# 07_AUDIO.net
KiCad netlist of a schematic drawn in Altium Designer
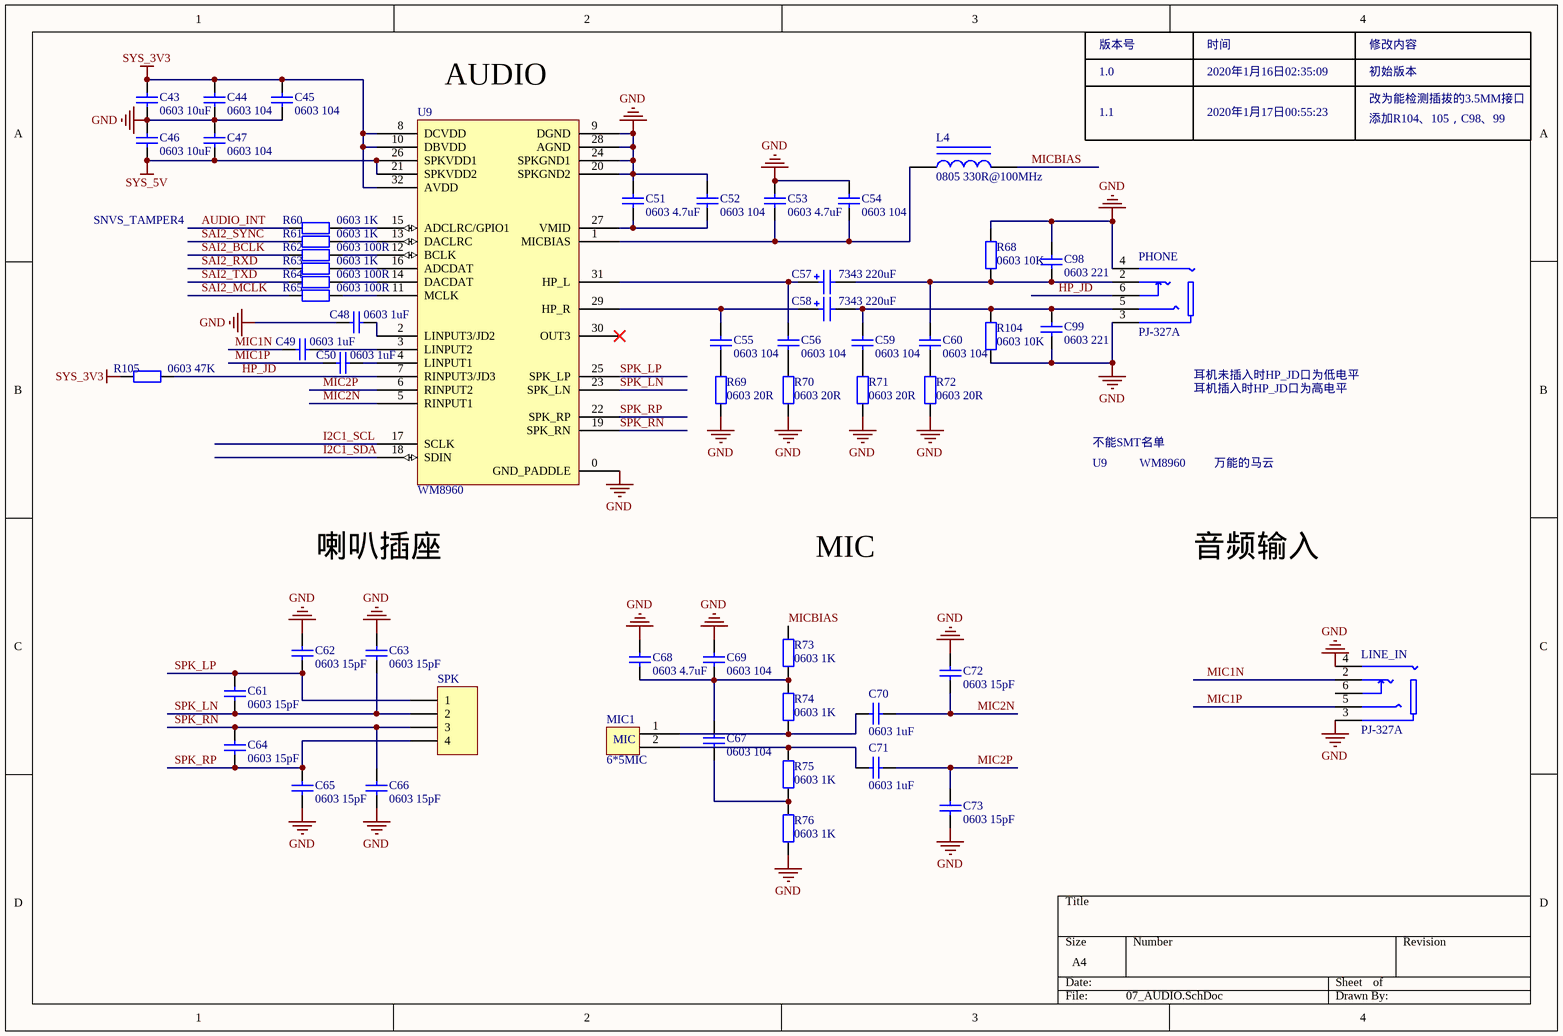
[diagram p0: 07_AUDIO.SchDoc]

(export (version "E")
  (design (tool "Eeschema 10.0.6"))
  (components
    (comp (ref "C43")
      (value "0603 10uF")
      (footprint "LC-0603_C")
      (description "贴片电容")
      (libsource (lib "JLC") (part "0603 1.5nF (152) 10% 50V"))
    )
    (comp (ref "C44")
      (value "0603 104")
      (footprint "LC-0603_C")
      (description "贴片电容")
      (libsource (lib "JLC") (part "0603 1.5nF (152) 10% 50V"))
    )
    (comp (ref "C45")
      (value "0603 104")
      (footprint "LC-0603_C")
      (description "贴片电容")
      (libsource (lib "JLC") (part "0603 1.5nF (152) 10% 50V"))
    )
    (comp (ref "C46")
      (value "0603 10uF")
      (footprint "LC-0603_C")
      (description "贴片电容")
      (libsource (lib "JLC") (part "0603 1.5nF (152) 10% 50V"))
    )
    (comp (ref "C47")
      (value "0603 104")
      (footprint "LC-0603_C")
      (description "贴片电容")
      (libsource (lib "JLC") (part "0603 1.5nF (152) 10% 50V"))
    )
    (comp (ref "C48")
      (value "0603 1uF")
      (footprint "LC-0603_C")
      (description "贴片电容")
      (libsource (lib "JLC") (part "0603 1.5nF (152) 10% 50V"))
    )
    (comp (ref "C49")
      (value "0603 1uF")
      (footprint "LC-0603_C")
      (description "贴片电容")
      (libsource (lib "JLC") (part "0603 1.5nF (152) 10% 50V"))
    )
    (comp (ref "C50")
      (value "0603 1uF")
      (footprint "LC-0603_C")
      (description "贴片电容")
      (libsource (lib "JLC") (part "0603 1.5nF (152) 10% 50V"))
    )
    (comp (ref "C51")
      (value "0603 4.7uF")
      (footprint "LC-0603_C")
      (description "贴片电容")
      (libsource (lib "JLC") (part "0603 1.5nF (152) 10% 50V"))
    )
    (comp (ref "C52")
      (value "0603 104")
      (footprint "LC-0603_C")
      (description "贴片电容")
      (libsource (lib "JLC") (part "0603 1.5nF (152) 10% 50V"))
    )
    (comp (ref "C53")
      (value "0603 4.7uF")
      (footprint "LC-0603_C")
      (description "贴片电容")
      (libsource (lib "JLC") (part "0603 1.5nF (152) 10% 50V"))
    )
    (comp (ref "C54")
      (value "0603 104")
      (footprint "LC-0603_C")
      (description "贴片电容")
      (libsource (lib "JLC") (part "0603 1.5nF (152) 10% 50V"))
    )
    (comp (ref "C55")
      (value "0603 104")
      (footprint "LC-0603_C")
      (description "贴片电容")
      (libsource (lib "JLC") (part "0603 1.5nF (152) 10% 50V"))
    )
    (comp (ref "C56")
      (value "0603 104")
      (footprint "LC-0603_C")
      (description "贴片电容")
      (libsource (lib "JLC") (part "0603 1.5nF (152) 10% 50V"))
    )
    (comp (ref "C57")
      (value "7343 220uF")
      (footprint "Ta7343")
      (libsource (lib "Integrated_Library2") (part "CAP1"))
    )
    (comp (ref "C58")
      (value "7343 220uF")
      (footprint "Ta7343")
      (libsource (lib "Integrated_Library2") (part "CAP1"))
    )
    (comp (ref "C59")
      (value "0603 104")
      (footprint "LC-0603_C")
      (description "贴片电容")
      (libsource (lib "JLC") (part "0603 1.5nF (152) 10% 50V"))
    )
    (comp (ref "C60")
      (value "0603 104")
      (footprint "LC-0603_C")
      (description "贴片电容")
      (libsource (lib "JLC") (part "0603 1.5nF (152) 10% 50V"))
    )
    (comp (ref "C61")
      (value "0603 15pF")
      (footprint "LC-0603_C")
      (description "贴片电容")
      (libsource (lib "JLC") (part "0603 1.5nF (152) 10% 50V"))
    )
    (comp (ref "C62")
      (value "0603 15pF")
      (footprint "LC-0603_C")
      (description "贴片电容")
      (libsource (lib "JLC") (part "0603 1.5nF (152) 10% 50V"))
    )
    (comp (ref "C63")
      (value "0603 15pF")
      (footprint "LC-0603_C")
      (description "贴片电容")
      (libsource (lib "JLC") (part "0603 1.5nF (152) 10% 50V"))
    )
    (comp (ref "C64")
      (value "0603 15pF")
      (footprint "LC-0603_C")
      (description "贴片电容")
      (libsource (lib "JLC") (part "0603 1.5nF (152) 10% 50V"))
    )
    (comp (ref "C65")
      (value "0603 15pF")
      (footprint "LC-0603_C")
      (description "贴片电容")
      (libsource (lib "JLC") (part "0603 1.5nF (152) 10% 50V"))
    )
    (comp (ref "C66")
      (value "0603 15pF")
      (footprint "LC-0603_C")
      (description "贴片电容")
      (libsource (lib "JLC") (part "0603 1.5nF (152) 10% 50V"))
    )
    (comp (ref "C67")
      (value "0603 104")
      (footprint "LC-0603_C")
      (description "贴片电容")
      (libsource (lib "JLC") (part "0603 1.5nF (152) 10% 50V"))
    )
    (comp (ref "C68")
      (value "0603 4.7uF")
      (footprint "LC-0603_C")
      (description "贴片电容")
      (libsource (lib "JLC") (part "0603 1.5nF (152) 10% 50V"))
    )
    (comp (ref "C69")
      (value "0603 104")
      (footprint "LC-0603_C")
      (description "贴片电容")
      (libsource (lib "JLC") (part "0603 1.5nF (152) 10% 50V"))
    )
    (comp (ref "C70")
      (value "0603 1uF")
      (footprint "LC-0603_C")
      (description "贴片电容")
      (libsource (lib "JLC") (part "0603 1.5nF (152) 10% 50V"))
    )
    (comp (ref "C71")
      (value "0603 1uF")
      (footprint "LC-0603_C")
      (description "贴片电容")
      (libsource (lib "JLC") (part "0603 1.5nF (152) 10% 50V"))
    )
    (comp (ref "C72")
      (value "0603 15pF")
      (footprint "LC-0603_C")
      (description "贴片电容")
      (libsource (lib "JLC") (part "0603 1.5nF (152) 10% 50V"))
    )
    (comp (ref "C73")
      (value "0603 15pF")
      (footprint "LC-0603_C")
      (description "贴片电容")
      (libsource (lib "JLC") (part "0603 1.5nF (152) 10% 50V"))
    )
    (comp (ref "C98")
      (value "0603 221")
      (footprint "LC-0603_C")
      (description "贴片电容")
      (libsource (lib "JLC") (part "0603 1.5nF (152) 10% 50V"))
    )
    (comp (ref "C99")
      (value "0603 221")
      (footprint "LC-0603_C")
      (description "贴片电容")
      (libsource (lib "JLC") (part "0603 1.5nF (152) 10% 50V"))
    )
    (comp (ref "L4")
      (value "0805 330R@100MHz")
      (footprint "LC-0805_L")
      (description "贴片电感")
      (libsource (lib "JLC") (part "0805 1uH 10%"))
    )
    (comp (ref "LINE_IN")
      (value "PJ-327A")
      (footprint "PJ-327A")
      (libsource (lib "Integrated_Library2") (part "PJ-327A"))
    )
    (comp (ref "MIC1")
      (value "6*5MIC")
      (footprint "6*5MIC")
      (libsource (lib "Integrated_Library2") (part "6*5MIC"))
    )
    (comp (ref "PHONE")
      (value "PJ-327A")
      (footprint "PJ-327A")
      (libsource (lib "Integrated_Library2") (part "PJ-327A"))
    )
    (comp (ref "R60")
      (value "0603 1K")
      (footprint "LC-0603_R")
      (description "贴片电阻")
      (libsource (lib "") (part "0603 1.1KΩ (1101) 1%_1"))
    )
    (comp (ref "R61")
      (value "0603 1K")
      (footprint "LC-0603_R")
      (description "贴片电阻")
      (libsource (lib "") (part "0603 1.1KΩ (1101) 1%_1"))
    )
    (comp (ref "R62")
      (value "0603 100R")
      (footprint "LC-0603_R")
      (description "贴片电阻")
      (libsource (lib "") (part "0603 1.1KΩ (1101) 1%_1"))
    )
    (comp (ref "R63")
      (value "0603 1K")
      (footprint "LC-0603_R")
      (description "贴片电阻")
      (libsource (lib "") (part "0603 1.1KΩ (1101) 1%_1"))
    )
    (comp (ref "R64")
      (value "0603 100R")
      (footprint "LC-0603_R")
      (description "贴片电阻")
      (libsource (lib "") (part "0603 1.1KΩ (1101) 1%_1"))
    )
    (comp (ref "R65")
      (value "0603 100R")
      (footprint "LC-0603_R")
      (description "贴片电阻")
      (libsource (lib "") (part "0603 1.1KΩ (1101) 1%_1"))
    )
    (comp (ref "R68")
      (value "0603 10K")
      (footprint "LC-0603_R")
      (description "贴片电阻")
      (libsource (lib "JLC") (part "0603 1.1KΩ (1101) 1%"))
    )
    (comp (ref "R69")
      (value "0603 20R")
      (footprint "LC-0603_R")
      (description "贴片电阻")
      (libsource (lib "JLC") (part "0603 1.1KΩ (1101) 1%"))
    )
    (comp (ref "R70")
      (value "0603 20R")
      (footprint "LC-0603_R")
      (description "贴片电阻")
      (libsource (lib "JLC") (part "0603 1.1KΩ (1101) 1%"))
    )
    (comp (ref "R71")
      (value "0603 20R")
      (footprint "LC-0603_R")
      (description "贴片电阻")
      (libsource (lib "JLC") (part "0603 1.1KΩ (1101) 1%"))
    )
    (comp (ref "R72")
      (value "0603 20R")
      (footprint "LC-0603_R")
      (description "贴片电阻")
      (libsource (lib "JLC") (part "0603 1.1KΩ (1101) 1%"))
    )
    (comp (ref "R73")
      (value "0603 1K")
      (footprint "LC-0603_R")
      (description "贴片电阻")
      (libsource (lib "JLC") (part "0603 1.1KΩ (1101) 1%"))
    )
    (comp (ref "R74")
      (value "0603 1K")
      (footprint "LC-0603_R")
      (description "贴片电阻")
      (libsource (lib "JLC") (part "0603 1.1KΩ (1101) 1%"))
    )
    (comp (ref "R75")
      (value "0603 1K")
      (footprint "LC-0603_R")
      (description "贴片电阻")
      (libsource (lib "JLC") (part "0603 1.1KΩ (1101) 1%"))
    )
    (comp (ref "R76")
      (value "0603 1K")
      (footprint "LC-0603_R")
      (description "贴片电阻")
      (libsource (lib "JLC") (part "0603 1.1KΩ (1101) 1%"))
    )
    (comp (ref "R104")
      (value "0603 10K")
      (footprint "LC-0603_R")
      (description "贴片电阻")
      (libsource (lib "") (part "0603 1.1KΩ (1101) 1%_2"))
    )
    (comp (ref "R105")
      (value "0603 47K")
      (footprint "LC-0603_R")
      (description "贴片电阻")
      (libsource (lib "") (part "0603 1.1KΩ (1101) 1%_1"))
    )
    (comp (ref "SPK")
      (value "~")
      (footprint "HDR1X4")
      (description "Header, 4-Pin")
      (fields (field (name "PUBLISHER") "Altium Limited"))
      (libsource (lib "Miscellaneous Connectors") (part "Header 4"))
    )
    (comp (ref "U9")
      (value "WM8960")
      (footprint "LC-QFN-32_5x5x05P")
      (libsource (lib "Integrated_Library2") (part "WM8960"))
    )
  )
  (nets
    (net (code "1") (name "/AUDIO_INT") (class "Default")
      (node (ref "R60") (pin "1") (pinfunction "1_1") (pintype "passive"))
    )
    (net (code "2") (name "/HP_JD") (class "Default")
      (node (ref "PHONE") (pin "6") (pinfunction "6_6") (pintype "passive"))
      (node (ref "R105") (pin "2") (pinfunction "2_2") (pintype "passive"))
      (node (ref "U9") (pin "7") (pinfunction "RINPUT3/JD3_7") (pintype "passive"))
    )
    (net (code "3") (name "/I2C1_SCL") (class "Default")
      (node (ref "U9") (pin "17") (pinfunction "SCLK_17") (pintype "passive"))
    )
    (net (code "4") (name "/I2C1_SDA") (class "Default")
      (node (ref "U9") (pin "18") (pinfunction "SDIN_18") (pintype "bidirectional"))
    )
    (net (code "5") (name "/MIC1N") (class "Default")
      (node (ref "C49") (pin "2") (pinfunction "2_2") (pintype "passive"))
      (node (ref "LINE_IN") (pin "2") (pinfunction "2_2") (pintype "passive"))
    )
    (net (code "6") (name "/MIC1P") (class "Default")
      (node (ref "C50") (pin "2") (pinfunction "2_2") (pintype "passive"))
      (node (ref "LINE_IN") (pin "5") (pinfunction "5_5") (pintype "passive"))
    )
    (net (code "7") (name "/MIC2N") (class "Default")
      (node (ref "C70") (pin "2") (pinfunction "2_2") (pintype "passive"))
      (node (ref "C72") (pin "1") (pinfunction "1_1") (pintype "passive"))
      (node (ref "U9") (pin "5") (pinfunction "RINPUT1_5") (pintype "passive"))
    )
    (net (code "8") (name "/MIC2P") (class "Default")
      (node (ref "C71") (pin "2") (pinfunction "2_2") (pintype "passive"))
      (node (ref "C73") (pin "2") (pinfunction "2_2") (pintype "passive"))
      (node (ref "U9") (pin "6") (pinfunction "RINPUT2_6") (pintype "passive"))
    )
    (net (code "9") (name "/MICBIAS") (class "Default")
      (node (ref "L4") (pin "2") (pinfunction "2_2") (pintype "passive"))
      (node (ref "R73") (pin "1") (pinfunction "1_1") (pintype "passive"))
    )
    (net (code "10") (name "/SAI2_BCLK") (class "Default")
      (node (ref "R62") (pin "1") (pinfunction "1_1") (pintype "passive"))
    )
    (net (code "11") (name "/SAI2_MCLK") (class "Default")
      (node (ref "R65") (pin "1") (pinfunction "1_1") (pintype "passive"))
    )
    (net (code "12") (name "/SAI2_RXD") (class "Default")
      (node (ref "R63") (pin "1") (pinfunction "1_1") (pintype "passive"))
    )
    (net (code "13") (name "/SAI2_SYNC") (class "Default")
      (node (ref "R61") (pin "1") (pinfunction "1_1") (pintype "passive"))
    )
    (net (code "14") (name "/SAI2_TXD") (class "Default")
      (node (ref "R64") (pin "1") (pinfunction "1_1") (pintype "passive"))
    )
    (net (code "15") (name "/SPK_LN") (class "Default")
      (node (ref "C61") (pin "2") (pinfunction "2_2") (pintype "passive"))
      (node (ref "C63") (pin "2") (pinfunction "2_2") (pintype "passive"))
      (node (ref "SPK") (pin "2") (pinfunction "2_2") (pintype "passive"))
      (node (ref "U9") (pin "23") (pinfunction "SPK_LN_23") (pintype "passive"))
    )
    (net (code "16") (name "/SPK_LP") (class "Default")
      (node (ref "C61") (pin "1") (pinfunction "1_1") (pintype "passive"))
      (node (ref "C62") (pin "2") (pinfunction "2_2") (pintype "passive"))
      (node (ref "SPK") (pin "1") (pinfunction "1_1") (pintype "passive"))
      (node (ref "U9") (pin "25") (pinfunction "SPK_LP_25") (pintype "passive"))
    )
    (net (code "17") (name "/SPK_RN") (class "Default")
      (node (ref "C64") (pin "2") (pinfunction "2_2") (pintype "passive"))
      (node (ref "C66") (pin "2") (pinfunction "2_2") (pintype "passive"))
      (node (ref "SPK") (pin "3") (pinfunction "3_3") (pintype "passive"))
      (node (ref "U9") (pin "19") (pinfunction "SPK_RN_19") (pintype "passive"))
    )
    (net (code "18") (name "/SPK_RP") (class "Default")
      (node (ref "C64") (pin "1") (pinfunction "1_1") (pintype "passive"))
      (node (ref "C65") (pin "2") (pinfunction "2_2") (pintype "passive"))
      (node (ref "SPK") (pin "4") (pinfunction "4_4") (pintype "passive"))
      (node (ref "U9") (pin "22") (pinfunction "SPK_RP_22") (pintype "passive"))
    )
    (net (code "19") (name "GND") (class "Default")
      (node (ref "C43") (pin "1") (pinfunction "1_1") (pintype "passive"))
      (node (ref "C44") (pin "1") (pinfunction "1_1") (pintype "passive"))
      (node (ref "C45") (pin "1") (pinfunction "1_1") (pintype "passive"))
      (node (ref "C46") (pin "2") (pinfunction "2_2") (pintype "passive"))
      (node (ref "C47") (pin "2") (pinfunction "2_2") (pintype "passive"))
      (node (ref "C48") (pin "2") (pinfunction "2_2") (pintype "passive"))
      (node (ref "C51") (pin "1") (pinfunction "1_1") (pintype "passive"))
      (node (ref "C52") (pin "1") (pinfunction "1_1") (pintype "passive"))
      (node (ref "C53") (pin "1") (pinfunction "1_1") (pintype "passive"))
      (node (ref "C54") (pin "1") (pinfunction "1_1") (pintype "passive"))
      (node (ref "C62") (pin "1") (pinfunction "1_1") (pintype "passive"))
      (node (ref "C63") (pin "1") (pinfunction "1_1") (pintype "passive"))
      (node (ref "C65") (pin "1") (pinfunction "1_1") (pintype "passive"))
      (node (ref "C66") (pin "1") (pinfunction "1_1") (pintype "passive"))
      (node (ref "C68") (pin "1") (pinfunction "1_1") (pintype "passive"))
      (node (ref "C69") (pin "1") (pinfunction "1_1") (pintype "passive"))
      (node (ref "C72") (pin "2") (pinfunction "2_2") (pintype "passive"))
      (node (ref "C73") (pin "1") (pinfunction "1_1") (pintype "passive"))
      (node (ref "C98") (pin "1") (pinfunction "1_1") (pintype "passive"))
      (node (ref "C99") (pin "2") (pinfunction "2_2") (pintype "passive"))
      (node (ref "LINE_IN") (pin "3") (pinfunction "3_3") (pintype "passive"))
      (node (ref "LINE_IN") (pin "4") (pinfunction "4_4") (pintype "passive"))
      (node (ref "PHONE") (pin "3") (pinfunction "3_3") (pintype "passive"))
      (node (ref "PHONE") (pin "4") (pinfunction "4_4") (pintype "passive"))
      (node (ref "R104") (pin "1") (pinfunction "1_1") (pintype "passive"))
      (node (ref "R68") (pin "1") (pinfunction "1_1") (pintype "passive"))
      (node (ref "R69") (pin "2") (pinfunction "2_2") (pintype "passive"))
      (node (ref "R70") (pin "2") (pinfunction "2_2") (pintype "passive"))
      (node (ref "R71") (pin "2") (pinfunction "2_2") (pintype "passive"))
      (node (ref "R72") (pin "2") (pinfunction "2_2") (pintype "passive"))
      (node (ref "R76") (pin "2") (pinfunction "2_2") (pintype "passive"))
      (node (ref "U9") (pin "0") (pinfunction "GND_PADDLE_0") (pintype "power_in"))
      (node (ref "U9") (pin "20") (pinfunction "SPKGND2_20") (pintype "power_in"))
      (node (ref "U9") (pin "24") (pinfunction "SPKGND1_24") (pintype "power_in"))
      (node (ref "U9") (pin "28") (pinfunction "AGND_28") (pintype "power_in"))
      (node (ref "U9") (pin "9") (pinfunction "DGND_9") (pintype "power_in"))
    )
    (net (code "20") (name "Net-(C55-Pad2)") (class "Default")
      (node (ref "C55") (pin "2") (pinfunction "2_2") (pintype "passive"))
      (node (ref "R69") (pin "1") (pinfunction "1_1") (pintype "passive"))
    )
    (net (code "21") (name "Net-(C56-Pad2)") (class "Default")
      (node (ref "C56") (pin "2") (pinfunction "2_2") (pintype "passive"))
      (node (ref "R70") (pin "1") (pinfunction "1_1") (pintype "passive"))
    )
    (net (code "22") (name "Net-(C57-Pad2)") (class "Default")
      (node (ref "C57") (pin "2") (pinfunction "2_2") (pintype "passive"))
      (node (ref "C60") (pin "1") (pinfunction "1_1") (pintype "passive"))
      (node (ref "C98") (pin "2") (pinfunction "2_2") (pintype "passive"))
      (node (ref "PHONE") (pin "2") (pinfunction "2_2") (pintype "passive"))
      (node (ref "R68") (pin "2") (pinfunction "2_2") (pintype "passive"))
    )
    (net (code "23") (name "Net-(C58-Pad2)") (class "Default")
      (node (ref "C58") (pin "2") (pinfunction "2_2") (pintype "passive"))
      (node (ref "C59") (pin "1") (pinfunction "1_1") (pintype "passive"))
      (node (ref "C99") (pin "1") (pinfunction "1_1") (pintype "passive"))
      (node (ref "PHONE") (pin "5") (pinfunction "5_5") (pintype "passive"))
      (node (ref "R104") (pin "2") (pinfunction "2_2") (pintype "passive"))
    )
    (net (code "24") (name "Net-(C59-Pad2)") (class "Default")
      (node (ref "C59") (pin "2") (pinfunction "2_2") (pintype "passive"))
      (node (ref "R71") (pin "1") (pinfunction "1_1") (pintype "passive"))
    )
    (net (code "25") (name "Net-(C60-Pad2)") (class "Default")
      (node (ref "C60") (pin "2") (pinfunction "2_2") (pintype "passive"))
      (node (ref "R72") (pin "1") (pinfunction "1_1") (pintype "passive"))
    )
    (net (code "26") (name "Net-(C67-Pad1)") (class "Default")
      (node (ref "C67") (pin "1") (pinfunction "1_1") (pintype "passive"))
      (node (ref "R75") (pin "2") (pinfunction "2_2") (pintype "passive"))
      (node (ref "R76") (pin "1") (pinfunction "1_1") (pintype "passive"))
    )
    (net (code "27") (name "Net-(C67-Pad2)") (class "Default")
      (node (ref "C67") (pin "2") (pinfunction "2_2") (pintype "passive"))
      (node (ref "C68") (pin "2") (pinfunction "2_2") (pintype "passive"))
      (node (ref "C69") (pin "2") (pinfunction "2_2") (pintype "passive"))
      (node (ref "R73") (pin "2") (pinfunction "2_2") (pintype "passive"))
      (node (ref "R74") (pin "1") (pinfunction "1_1") (pintype "passive"))
    )
    (net (code "28") (name "Net-(MIC1-11)") (class "Default")
      (node (ref "C70") (pin "1") (pinfunction "1_1") (pintype "passive"))
      (node (ref "MIC1") (pin "1") (pinfunction "11_1") (pintype "passive"))
      (node (ref "R74") (pin "2") (pinfunction "2_2") (pintype "passive"))
    )
    (net (code "29") (name "Net-(MIC1-12)") (class "Default")
      (node (ref "C71") (pin "1") (pinfunction "1_1") (pintype "passive"))
      (node (ref "MIC1") (pin "2") (pinfunction "12_2") (pintype "passive"))
      (node (ref "R75") (pin "1") (pinfunction "1_1") (pintype "passive"))
    )
    (net (code "30") (name "Net-(U9-ADCDAT)") (class "Default")
      (node (ref "R63") (pin "2") (pinfunction "2_2") (pintype "passive"))
      (node (ref "U9") (pin "16") (pinfunction "ADCDAT_16") (pintype "passive"))
    )
    (net (code "31") (name "Net-(U9-ADCLRC{slash}GPIO1)") (class "Default")
      (node (ref "R60") (pin "2") (pinfunction "2_2") (pintype "passive"))
      (node (ref "U9") (pin "15") (pinfunction "ADCLRC/GPIO1_15") (pintype "bidirectional"))
    )
    (net (code "32") (name "Net-(U9-BCLK)") (class "Default")
      (node (ref "R62") (pin "2") (pinfunction "2_2") (pintype "passive"))
      (node (ref "U9") (pin "12") (pinfunction "BCLK_12") (pintype "bidirectional"))
    )
    (net (code "33") (name "Net-(U9-DACDAT)") (class "Default")
      (node (ref "R64") (pin "2") (pinfunction "2_2") (pintype "passive"))
      (node (ref "U9") (pin "14") (pinfunction "DACDAT_14") (pintype "passive"))
    )
    (net (code "34") (name "Net-(U9-DACLRC)") (class "Default")
      (node (ref "R61") (pin "2") (pinfunction "2_2") (pintype "passive"))
      (node (ref "U9") (pin "13") (pinfunction "DACLRC_13") (pintype "bidirectional"))
    )
    (net (code "35") (name "Net-(U9-HP_L)") (class "Default")
      (node (ref "C56") (pin "1") (pinfunction "1_1") (pintype "passive"))
      (node (ref "C57") (pin "1") (pinfunction "1_1") (pintype "passive"))
      (node (ref "U9") (pin "31") (pinfunction "HP_L_31") (pintype "passive"))
    )
    (net (code "36") (name "Net-(U9-HP_R)") (class "Default")
      (node (ref "C55") (pin "1") (pinfunction "1_1") (pintype "passive"))
      (node (ref "C58") (pin "1") (pinfunction "1_1") (pintype "passive"))
      (node (ref "U9") (pin "29") (pinfunction "HP_R_29") (pintype "passive"))
    )
    (net (code "37") (name "Net-(U9-LINPUT1)") (class "Default")
      (node (ref "C50") (pin "1") (pinfunction "1_1") (pintype "passive"))
      (node (ref "U9") (pin "4") (pinfunction "LINPUT1_4") (pintype "passive"))
    )
    (net (code "38") (name "Net-(U9-LINPUT2)") (class "Default")
      (node (ref "C49") (pin "1") (pinfunction "1_1") (pintype "passive"))
      (node (ref "U9") (pin "3") (pinfunction "LINPUT2_3") (pintype "passive"))
    )
    (net (code "39") (name "Net-(U9-LINPUT3{slash}JD2)") (class "Default")
      (node (ref "C48") (pin "1") (pinfunction "1_1") (pintype "passive"))
      (node (ref "U9") (pin "2") (pinfunction "LINPUT3/JD2_2") (pintype "passive"))
    )
    (net (code "40") (name "Net-(U9-MCLK)") (class "Default")
      (node (ref "R65") (pin "2") (pinfunction "2_2") (pintype "passive"))
      (node (ref "U9") (pin "11") (pinfunction "MCLK_11") (pintype "passive"))
    )
    (net (code "41") (name "Net-(U9-MICBIAS)") (class "Default")
      (node (ref "C53") (pin "2") (pinfunction "2_2") (pintype "passive"))
      (node (ref "C54") (pin "2") (pinfunction "2_2") (pintype "passive"))
      (node (ref "L4") (pin "1") (pinfunction "1_1") (pintype "passive"))
      (node (ref "U9") (pin "1") (pinfunction "MICBIAS_1") (pintype "passive"))
    )
    (net (code "42") (name "Net-(U9-VMID)") (class "Default")
      (node (ref "C51") (pin "2") (pinfunction "2_2") (pintype "passive"))
      (node (ref "C52") (pin "2") (pinfunction "2_2") (pintype "passive"))
      (node (ref "U9") (pin "27") (pinfunction "VMID_27") (pintype "passive"))
    )
    (net (code "43") (name "SYS_3V3") (class "Default")
      (node (ref "C43") (pin "2") (pinfunction "2_2") (pintype "passive"))
      (node (ref "C44") (pin "2") (pinfunction "2_2") (pintype "passive"))
      (node (ref "C45") (pin "2") (pinfunction "2_2") (pintype "passive"))
      (node (ref "R105") (pin "1") (pinfunction "1_1") (pintype "passive"))
      (node (ref "U9") (pin "10") (pinfunction "DBVDD_10") (pintype "power_in"))
      (node (ref "U9") (pin "32") (pinfunction "AVDD_32") (pintype "power_in"))
      (node (ref "U9") (pin "8") (pinfunction "DCVDD_8") (pintype "power_in"))
    )
    (net (code "44") (name "SYS_5V") (class "Default")
      (node (ref "C46") (pin "1") (pinfunction "1_1") (pintype "passive"))
      (node (ref "C47") (pin "1") (pinfunction "1_1") (pintype "passive"))
      (node (ref "U9") (pin "21") (pinfunction "SPKVDD2_21") (pintype "power_in"))
      (node (ref "U9") (pin "26") (pinfunction "SPKVDD1_26") (pintype "power_in"))
    )
    (net (code "45") (name "unconnected-(LINE_IN-Pad6)") (class "Default")
      (node (ref "LINE_IN") (pin "6") (pinfunction "6_6") (pintype "passive"))
    )
    (net (code "46") (name "unconnected-(U9-OUT3-Pad30)") (class "Default")
      (node (ref "U9") (pin "30") (pinfunction "OUT3_30") (pintype "passive+no_connect"))
    )
  )
)
